# Power_ToOctoPi.net
KiCad netlist of a schematic drawn in EAGLE
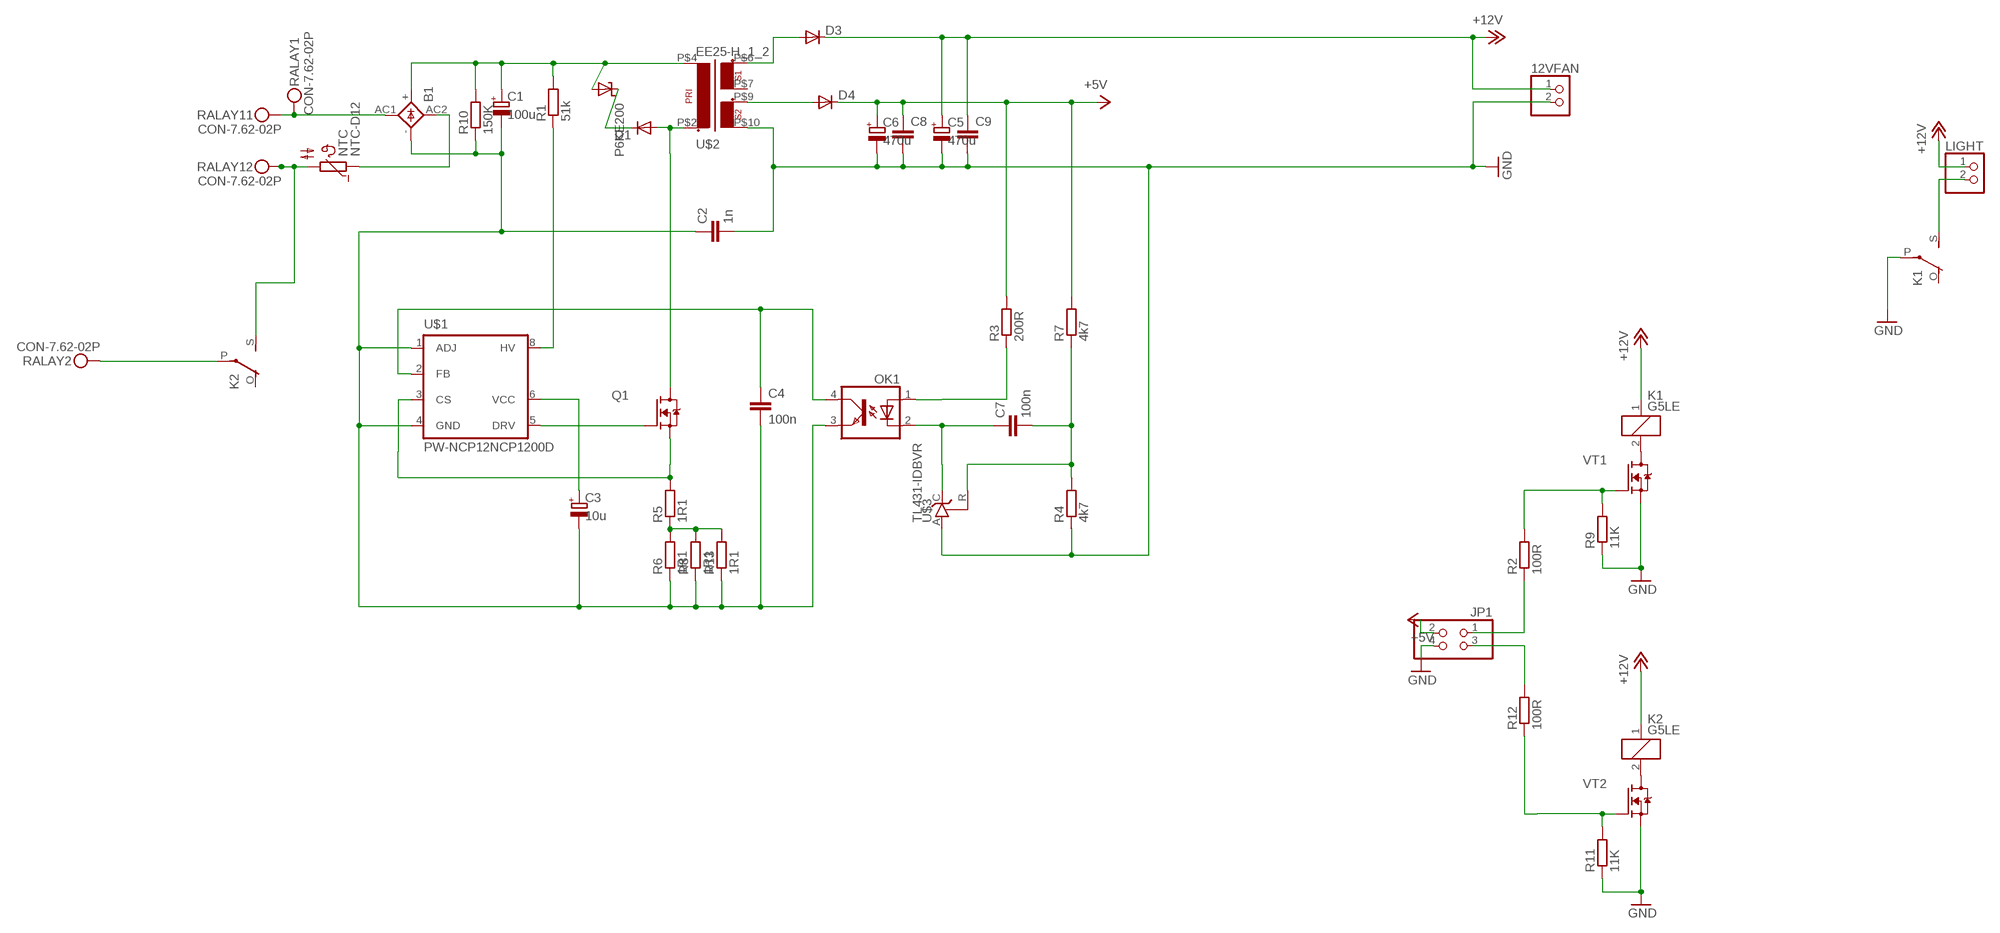
[diagram p0: schematic, sheet 1]

(export (version "E")
  (design (tool "Eeschema 10.0.6"))
  (components
    (comp (ref "12VFAN")
      (value "PINHD-1X2")
      (footprint "eagle-import:1X02")
      (libsource (lib "eagle-import") (part "PINHD-1X2"))
    )
    (comp (ref "B1")
      (value "KBL")
      (footprint "eagle-import:KBL")
      (libsource (lib "eagle-import") (part "KBL"))
    )
    (comp (ref "C1")
      (value "100u")
      (footprint "eagle-import:C_D25-G10-CLAMP")
      (libsource (lib "eagle-import") (part "CAP-POL_E25-10-C"))
    )
    (comp (ref "C2")
      (value "1n")
      (footprint "eagle-import:C050-024X044")
      (libsource (lib "eagle-import") (part "CAP_C50-024X044"))
    )
    (comp (ref "C3")
      (value "10u")
      (footprint "eagle-import:E2,5-7")
      (libsource (lib "eagle-import") (part "CAP-POL_E2.5-7"))
    )
    (comp (ref "C4")
      (value "100n")
      (footprint "eagle-import:C1206")
      (libsource (lib "eagle-import") (part "C-EUC1206"))
    )
    (comp (ref "C5")
      (value "470u")
      (footprint "eagle-import:E5-10,5")
      (libsource (lib "eagle-import") (part "CAP-POL_E5-10.5"))
    )
    (comp (ref "C6")
      (value "470u")
      (footprint "eagle-import:E5-10,5")
      (libsource (lib "eagle-import") (part "CAP-POL_E5-10.5"))
    )
    (comp (ref "C7")
      (value "100n")
      (footprint "eagle-import:C1206")
      (libsource (lib "eagle-import") (part "C-EUC1206"))
    )
    (comp (ref "C8")
      (value "CAP_0805")
      (footprint "eagle-import:C0805")
      (libsource (lib "eagle-import") (part "CAP_0805"))
    )
    (comp (ref "C9")
      (value "CAP_0805")
      (footprint "eagle-import:C0805")
      (libsource (lib "eagle-import") (part "CAP_0805"))
    )
    (comp (ref "D1")
      (value "DIODE_ES1J")
      (footprint "eagle-import:DO214AC")
      (libsource (lib "eagle-import") (part "DIODE_ES1J"))
    )
    (comp (ref "D3")
      (value "DIODE_ES1J")
      (footprint "eagle-import:DO214AC")
      (libsource (lib "eagle-import") (part "DIODE_ES1J"))
    )
    (comp (ref "D4")
      (value "DIODE_ES1J")
      (footprint "eagle-import:DO214AC")
      (libsource (lib "eagle-import") (part "DIODE_ES1J"))
    )
    (comp (ref "JP1")
      (value "PINHD-2X2")
      (footprint "eagle-import:2X02")
      (libsource (lib "eagle-import") (part "PINHD-2X2"))
    )
    (comp (ref "K1")
      (value "G5LE")
      (footprint "eagle-import:G5LE")
      (libsource (lib "eagle-import") (part "G5LE"))
    )
    (comp (ref "K2")
      (value "G5LE")
      (footprint "eagle-import:G5LE")
      (libsource (lib "eagle-import") (part "G5LE"))
    )
    (comp (ref "LIGHT")
      (value "PINHD-1X2")
      (footprint "eagle-import:1X02")
      (libsource (lib "eagle-import") (part "PINHD-1X2"))
    )
    (comp (ref "NTC")
      (value "NTC-D12")
      (footprint "eagle-import:NTC-D12")
      (libsource (lib "eagle-import") (part "NTC-D12"))
    )
    (comp (ref "OK1")
      (value "OPTOTRANSPC817")
      (footprint "eagle-import:DIL04")
      (fields (field (name "MPN") "PC817X4J000F"))
      (libsource (lib "eagle-import") (part "OPTOTRANSPC817"))
    )
    (comp (ref "P6KE200")
      (value "SUPRESSORDO-204AC")
      (footprint "eagle-import:DO15-12")
      (libsource (lib "eagle-import") (part "SUPRESSORDO-204AC"))
    )
    (comp (ref "Q1")
      (value "FET-NTO-220")
      (footprint "eagle-import:TO-220V")
      (libsource (lib "eagle-import") (part "FET-NTO-220"))
    )
    (comp (ref "R1")
      (value "51k")
      (footprint "eagle-import:SQP-5")
      (libsource (lib "eagle-import") (part "R_SQP-5"))
    )
    (comp (ref "R2")
      (value "100R")
      (footprint "eagle-import:R0805")
      (libsource (lib "eagle-import") (part "R_0805"))
    )
    (comp (ref "R3")
      (value "200R")
      (footprint "eagle-import:R1206")
      (libsource (lib "eagle-import") (part "R-EU_R1206"))
    )
    (comp (ref "R4")
      (value "4k7")
      (footprint "eagle-import:R1206")
      (libsource (lib "eagle-import") (part "R-EU_R1206"))
    )
    (comp (ref "R5")
      (value "1R1")
      (footprint "eagle-import:R1206")
      (libsource (lib "eagle-import") (part "R-EU_R1206"))
    )
    (comp (ref "R6")
      (value "1R1")
      (footprint "eagle-import:R1206")
      (libsource (lib "eagle-import") (part "R-EU_R1206"))
    )
    (comp (ref "R7")
      (value "4k7")
      (footprint "eagle-import:R1206")
      (libsource (lib "eagle-import") (part "R-EU_R1206"))
    )
    (comp (ref "R8")
      (value "1R1")
      (footprint "eagle-import:R1206")
      (libsource (lib "eagle-import") (part "R-EU_R1206"))
    )
    (comp (ref "R9")
      (value "11K")
      (footprint "eagle-import:R0805")
      (libsource (lib "eagle-import") (part "R_0805"))
    )
    (comp (ref "R10")
      (value "150K")
      (footprint "eagle-import:MF-0125")
      (libsource (lib "eagle-import") (part "R_MF-0125"))
    )
    (comp (ref "R11")
      (value "11K")
      (footprint "eagle-import:R0805")
      (libsource (lib "eagle-import") (part "R_0805"))
    )
    (comp (ref "R12")
      (value "100R")
      (footprint "eagle-import:R0805")
      (libsource (lib "eagle-import") (part "R_0805"))
    )
    (comp (ref "R13")
      (value "1R1")
      (footprint "eagle-import:R1206")
      (libsource (lib "eagle-import") (part "R-EU_R1206"))
    )
    (comp (ref "RALAY")
      (value "CON-7.62-02P")
      (footprint "eagle-import:KF25C-7.62-02P-13")
      (libsource (lib "eagle-import") (part "CON-7.62-02P"))
    )
    (comp (ref "RALAY1")
      (value "CON-7.62-02P")
      (footprint "eagle-import:KF25C-7.62-02P-13")
      (libsource (lib "eagle-import") (part "CON-7.62-02P"))
    )
    (comp (ref "U$1")
      (value "PW-NCP12NCP1200D")
      (footprint "eagle-import:SO8")
      (libsource (lib "eagle-import") (part "PW-NCP12NCP1200D"))
    )
    (comp (ref "U$2")
      (value "EE25-H_1_2")
      (footprint "eagle-import:EE25")
      (libsource (lib "eagle-import") (part "EE25-H_1_2"))
    )
    (comp (ref "U$3")
      (value "TL431-IDBVR")
      (footprint "eagle-import:SOT23-5")
      (libsource (lib "eagle-import") (part "TL431-IDBVR"))
    )
    (comp (ref "VT1")
      (value "FET-NPF-6X5")
      (footprint "eagle-import:POWERFLAT-5X6")
      (libsource (lib "eagle-import") (part "FET-NPF-6X5"))
    )
    (comp (ref "VT2")
      (value "FET-NPF-6X5")
      (footprint "eagle-import:POWERFLAT-5X6")
      (libsource (lib "eagle-import") (part "FET-NPF-6X5"))
    )
  )
  (nets
    (net (code "1") (name "+5V") (class "Default")
      (node (ref "C6") (pin "+") (pinfunction "+_+") (pintype "passive"))
      (node (ref "C8") (pin "1") (pinfunction "1_1") (pintype "passive"))
      (node (ref "D4") (pin "C") (pinfunction "C_C") (pintype "passive"))
      (node (ref "JP1") (pin "2") (pinfunction "2_2") (pintype "passive"))
      (node (ref "R3") (pin "2") (pinfunction "2_2") (pintype "passive"))
      (node (ref "R7") (pin "2") (pinfunction "2_2") (pintype "passive"))
    )
    (net (code "2") (name "+12V") (class "Default")
      (node (ref "12VFAN") (pin "1") (pinfunction "1_1") (pintype "passive"))
      (node (ref "C5") (pin "+") (pinfunction "+_+") (pintype "passive"))
      (node (ref "C9") (pin "1") (pinfunction "1_1") (pintype "passive"))
      (node (ref "D3") (pin "C") (pinfunction "C_C") (pintype "passive"))
      (node (ref "K1") (pin "1") (pinfunction "1_1") (pintype "passive"))
      (node (ref "K2") (pin "1") (pinfunction "1_1") (pintype "passive"))
      (node (ref "LIGHT") (pin "1") (pinfunction "1_1") (pintype "passive"))
    )
    (net (code "3") (name "GND") (class "Default")
      (node (ref "12VFAN") (pin "2") (pinfunction "2_2") (pintype "passive"))
      (node (ref "C2") (pin "2") (pinfunction "2_2") (pintype "passive"))
      (node (ref "C5") (pin "-") (pinfunction "-_-") (pintype "passive"))
      (node (ref "C6") (pin "-") (pinfunction "-_-") (pintype "passive"))
      (node (ref "C8") (pin "2") (pinfunction "2_2") (pintype "passive"))
      (node (ref "C9") (pin "2") (pinfunction "2_2") (pintype "passive"))
      (node (ref "JP1") (pin "4") (pinfunction "4_4") (pintype "passive"))
      (node (ref "K1") (pin "P") (pinfunction "P_P") (pintype "passive"))
      (node (ref "R11") (pin "1") (pinfunction "1_1") (pintype "passive"))
      (node (ref "R4") (pin "1") (pinfunction "1_1") (pintype "passive"))
      (node (ref "R9") (pin "1") (pinfunction "1_1") (pintype "passive"))
      (node (ref "U$2") (pin "P$10") (pinfunction "6_P$10") (pintype "passive"))
      (node (ref "U$3") (pin "A") (pinfunction "A_A") (pintype "passive"))
      (node (ref "VT1") (pin "S1") (pinfunction "S_S1") (pintype "passive"))
      (node (ref "VT1") (pin "S2") (pinfunction "S_S2") (pintype "passive"))
      (node (ref "VT1") (pin "S3") (pinfunction "S_S3") (pintype "passive"))
      (node (ref "VT2") (pin "S1") (pinfunction "S_S1") (pintype "passive"))
      (node (ref "VT2") (pin "S2") (pinfunction "S_S2") (pintype "passive"))
      (node (ref "VT2") (pin "S3") (pinfunction "S_S3") (pintype "passive"))
    )
    (net (code "4") (name "Net-(B1-AC1)") (class "Default")
      (node (ref "B1") (pin "AC2") (pinfunction "AC1_AC2") (pintype "passive"))
      (node (ref "NTC") (pin "1") (pinfunction "1_1") (pintype "passive"))
    )
    (net (code "5") (name "Net-(B1-AC2)") (class "Default")
      (node (ref "B1") (pin "AC1") (pinfunction "AC2_AC1") (pintype "passive"))
      (node (ref "RALAY") (pin "P$1") (pinfunction "KL_P$1") (pintype "passive"))
      (node (ref "RALAY1") (pin "P$1") (pinfunction "KL_P$1") (pintype "passive"))
    )
    (net (code "6") (name "Net-(C7-Pad2)") (class "Default")
      (node (ref "C7") (pin "2") (pinfunction "2_2") (pintype "passive"))
      (node (ref "R4") (pin "2") (pinfunction "2_2") (pintype "passive"))
      (node (ref "R7") (pin "1") (pinfunction "1_1") (pintype "passive"))
      (node (ref "U$3") (pin "R") (pinfunction "R_R") (pintype "passive"))
    )
    (net (code "7") (name "Net-(D1-PadC)") (class "Default")
      (node (ref "D1") (pin "C") (pinfunction "C_C") (pintype "passive"))
      (node (ref "P6KE200") (pin "C") (pinfunction "C_C") (pintype "passive"))
    )
    (net (code "8") (name "Net-(JP1-Pad1)") (class "Default")
      (node (ref "JP1") (pin "1") (pinfunction "1_1") (pintype "passive"))
      (node (ref "R2") (pin "1") (pinfunction "1_1") (pintype "passive"))
    )
    (net (code "9") (name "Net-(JP1-Pad3)") (class "Default")
      (node (ref "JP1") (pin "3") (pinfunction "3_3") (pintype "passive"))
      (node (ref "R12") (pin "2") (pinfunction "2_2") (pintype "passive"))
    )
    (net (code "10") (name "Net-(K1-PadS)") (class "Default")
      (node (ref "K1") (pin "S") (pinfunction "S_S") (pintype "passive"))
      (node (ref "LIGHT") (pin "2") (pinfunction "2_2") (pintype "passive"))
    )
    (net (code "11") (name "Net-(OK1-A)") (class "Default")
      (node (ref "OK1") (pin "1") (pinfunction "A_1") (pintype "passive"))
      (node (ref "R3") (pin "1") (pinfunction "1_1") (pintype "passive"))
    )
    (net (code "12") (name "Net-(OK1-C)") (class "Default")
      (node (ref "C7") (pin "1") (pinfunction "1_1") (pintype "passive"))
      (node (ref "OK1") (pin "2") (pinfunction "C_2") (pintype "passive"))
      (node (ref "U$3") (pin "C") (pinfunction "C_C") (pintype "passive"))
    )
    (net (code "13") (name "Net-(OK1-COL)") (class "Default")
      (node (ref "C4") (pin "1") (pinfunction "1_1") (pintype "passive"))
      (node (ref "OK1") (pin "4") (pinfunction "COL_4") (pintype "passive"))
      (node (ref "U$1") (pin "2") (pinfunction "FB_2") (pintype "input"))
    )
    (net (code "14") (name "Net-(OK1-EMIT)") (class "Default")
      (node (ref "B1") (pin "-") (pinfunction "-_-") (pintype "passive"))
      (node (ref "C1") (pin "-") (pinfunction "-_-") (pintype "passive"))
      (node (ref "C2") (pin "1") (pinfunction "1_1") (pintype "passive"))
      (node (ref "C3") (pin "-") (pinfunction "-_-") (pintype "passive"))
      (node (ref "C4") (pin "2") (pinfunction "2_2") (pintype "passive"))
      (node (ref "OK1") (pin "3") (pinfunction "EMIT_3") (pintype "passive"))
      (node (ref "R10") (pin "1") (pinfunction "1_1") (pintype "passive"))
      (node (ref "R13") (pin "1") (pinfunction "1_1") (pintype "passive"))
      (node (ref "R6") (pin "1") (pinfunction "1_1") (pintype "passive"))
      (node (ref "R8") (pin "1") (pinfunction "1_1") (pintype "passive"))
      (node (ref "U$1") (pin "1") (pinfunction "ADJ_1") (pintype "passive"))
      (node (ref "U$1") (pin "4") (pinfunction "GND_4") (pintype "passive"))
    )
    (net (code "15") (name "Net-(Q1-D)") (class "Default")
      (node (ref "D1") (pin "A") (pinfunction "A_A") (pintype "passive"))
      (node (ref "Q1") (pin "2") (pinfunction "D_2") (pintype "passive"))
      (node (ref "U$2") (pin "P$2") (pinfunction "1_P$2") (pintype "passive"))
    )
    (net (code "16") (name "Net-(Q1-G)") (class "Default")
      (node (ref "Q1") (pin "1") (pinfunction "G_1") (pintype "passive"))
      (node (ref "U$1") (pin "5") (pinfunction "DRV_5") (pintype "power_in"))
    )
    (net (code "17") (name "Net-(Q1-S)") (class "Default")
      (node (ref "Q1") (pin "3") (pinfunction "S_3") (pintype "passive"))
      (node (ref "R5") (pin "2") (pinfunction "2_2") (pintype "passive"))
      (node (ref "U$1") (pin "3") (pinfunction "CS_3") (pintype "input"))
    )
    (net (code "18") (name "Net-(R2-Pad2)") (class "Default")
      (node (ref "R2") (pin "2") (pinfunction "2_2") (pintype "passive"))
      (node (ref "R9") (pin "2") (pinfunction "2_2") (pintype "passive"))
      (node (ref "VT1") (pin "G") (pinfunction "G_G") (pintype "passive"))
    )
    (net (code "19") (name "Net-(R11-Pad2)") (class "Default")
      (node (ref "R11") (pin "2") (pinfunction "2_2") (pintype "passive"))
      (node (ref "R12") (pin "1") (pinfunction "1_1") (pintype "passive"))
      (node (ref "VT2") (pin "G") (pinfunction "G_G") (pintype "passive"))
    )
    (net (code "20") (name "Net-(R13-Pad2)") (class "Default")
      (node (ref "R13") (pin "2") (pinfunction "2_2") (pintype "passive"))
      (node (ref "R5") (pin "1") (pinfunction "1_1") (pintype "passive"))
      (node (ref "R6") (pin "2") (pinfunction "2_2") (pintype "passive"))
      (node (ref "R8") (pin "2") (pinfunction "2_2") (pintype "passive"))
    )
    (net (code "21") (name "Net-(RALAY1B-KL)") (class "Default")
      (node (ref "K2") (pin "S") (pinfunction "S_S") (pintype "passive"))
      (node (ref "NTC") (pin "2") (pinfunction "2_2") (pintype "passive"))
      (node (ref "RALAY1") (pin "P$2") (pinfunction "KL_P$2") (pintype "passive"))
    )
    (net (code "22") (name "Net-(RALAYB-KL)") (class "Default")
      (node (ref "K2") (pin "P") (pinfunction "P_P") (pintype "passive"))
      (node (ref "RALAY") (pin "P$2") (pinfunction "KL_P$2") (pintype "passive"))
    )
    (net (code "23") (name "Net-(U$1-HV)") (class "Default")
      (node (ref "R1") (pin "1") (pinfunction "1_1") (pintype "passive"))
      (node (ref "U$1") (pin "8") (pinfunction "HV_8") (pintype "passive"))
    )
    (net (code "24") (name "Net-(U$1-VCC)") (class "Default")
      (node (ref "C3") (pin "+") (pinfunction "+_+") (pintype "passive"))
      (node (ref "U$1") (pin "6") (pinfunction "VCC_6") (pintype "output"))
    )
    (net (code "25") (name "Net-(U$2-2)") (class "Default")
      (node (ref "B1") (pin "+") (pinfunction "+_+") (pintype "passive"))
      (node (ref "C1") (pin "+") (pinfunction "+_+") (pintype "passive"))
      (node (ref "P6KE200") (pin "A") (pinfunction "A_A") (pintype "passive"))
      (node (ref "R1") (pin "2") (pinfunction "2_2") (pintype "passive"))
      (node (ref "R10") (pin "2") (pinfunction "2_2") (pintype "passive"))
      (node (ref "U$2") (pin "P$4") (pinfunction "2_P$4") (pintype "passive"))
    )
    (net (code "26") (name "Net-(U$2-3)") (class "Default")
      (node (ref "D3") (pin "A") (pinfunction "A_A") (pintype "passive"))
      (node (ref "U$2") (pin "P$6") (pinfunction "3_P$6") (pintype "passive"))
    )
    (net (code "27") (name "Net-(U$2-5)") (class "Default")
      (node (ref "D4") (pin "A") (pinfunction "A_A") (pintype "passive"))
      (node (ref "U$2") (pin "P$9") (pinfunction "5_P$9") (pintype "passive"))
    )
    (net (code "28") (name "Net-(VT1-D)") (class "Default")
      (node (ref "K1") (pin "2") (pinfunction "2_2") (pintype "passive"))
      (node (ref "VT1") (pin "D1") (pinfunction "D_D1") (pintype "passive"))
    )
    (net (code "29") (name "Net-(VT2-D)") (class "Default")
      (node (ref "K2") (pin "2") (pinfunction "2_2") (pintype "passive"))
      (node (ref "VT2") (pin "D1") (pinfunction "D_D1") (pintype "passive"))
    )
    (net (code "30") (name "unconnected-(K1-PadO)") (class "Default")
      (node (ref "K1") (pin "O") (pinfunction "O_O") (pintype "passive"))
    )
    (net (code "31") (name "unconnected-(K2-PadO)") (class "Default")
      (node (ref "K2") (pin "O") (pinfunction "O_O") (pintype "passive"))
    )
    (net (code "32") (name "unconnected-(U$2-4-PadP$7)") (class "Default")
      (node (ref "U$2") (pin "P$7") (pinfunction "4_P$7") (pintype "passive"))
    )
  )
)
